# TYPEC0.net
KiCad netlist of a schematic drawn in Altium Designer
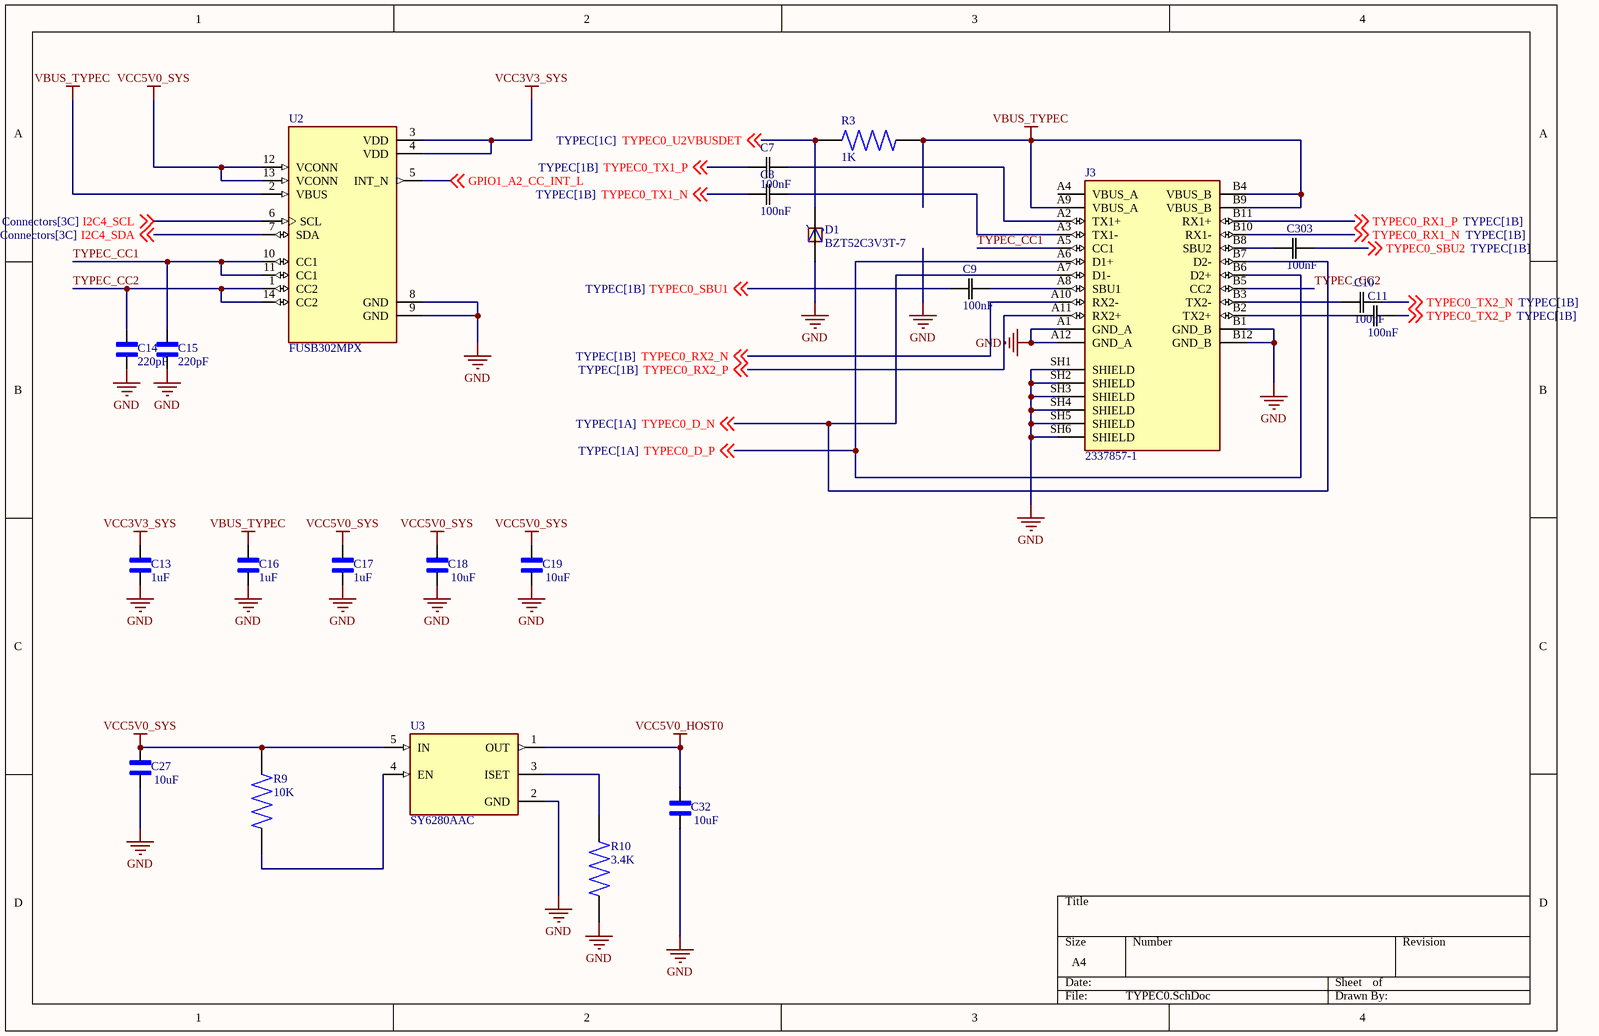
[diagram p0: TYPEC0.SchDoc]

(export (version "E")
  (design (tool "Eeschema 10.0.6"))
  (components
    (comp (ref "C7")
      (value "100nF")
      (footprint "CAP_1005_TDK")
      (description "Description")
      (fields
        (field (name "MANUFACTURER_PART_NUMBER") "C1005X7R1H104M050BB")
        (field (name "COPYRIGHT") "Copyright (C) 2025 Ultra Librarian. All rights reserved.")
      )
      (libsource (lib "C1005X7R1H104M050BB") (part "C1005X7R1H104M050BB"))
    )
    (comp (ref "C8")
      (value "100nF")
      (footprint "CAP_1005_TDK")
      (description "Description")
      (fields
        (field (name "MANUFACTURER_PART_NUMBER") "C1005X7R1H104M050BB")
        (field (name "COPYRIGHT") "Copyright (C) 2025 Ultra Librarian. All rights reserved.")
      )
      (libsource (lib "C1005X7R1H104M050BB") (part "C1005X7R1H104M050BB"))
    )
    (comp (ref "C9")
      (value "100nF")
      (footprint "CAP_1005_TDK")
      (description "Description")
      (fields
        (field (name "MANUFACTURER_PART_NUMBER") "C1005X7R1H104M050BB")
        (field (name "COPYRIGHT") "Copyright (C) 2025 Ultra Librarian. All rights reserved.")
      )
      (libsource (lib "C1005X7R1H104M050BB") (part "C1005X7R1H104M050BB"))
    )
    (comp (ref "C10")
      (value "100nF")
      (footprint "CAP_1005_TDK")
      (description "Description")
      (fields
        (field (name "MANUFACTURER_PART_NUMBER") "C1005X7R1H104M050BB")
        (field (name "COPYRIGHT") "Copyright (C) 2025 Ultra Librarian. All rights reserved.")
      )
      (libsource (lib "C1005X7R1H104M050BB") (part "C1005X7R1H104M050BB"))
    )
    (comp (ref "C11")
      (value "100nF")
      (footprint "CAP_1005_TDK")
      (description "Description")
      (fields
        (field (name "MANUFACTURER_PART_NUMBER") "C1005X7R1H104M050BB")
        (field (name "COPYRIGHT") "Copyright (C) 2025 Ultra Librarian. All rights reserved.")
      )
      (libsource (lib "C1005X7R1H104M050BB") (part "C1005X7R1H104M050BB"))
    )
    (comp (ref "C13")
      (value "1uF")
      (footprint "CAPC1005X56N")
      (description "1 ÂµF Â±10% 10V Ceramic Capacitor X5R 0402 (1005 Metric)")
      (fields (field (name "MF") "AVX") (field (name "MP") "0402ZD105KAT4A"))
      (libsource (lib "0402ZD105KAT4A") (part "0402ZD105KAT4A"))
    )
    (comp (ref "C14")
      (value "220pF")
      (footprint "CAPC1608X90")
      (description "220 pF Â±10% 16V Ceramic Capacitor X7R 0603 (1608 Metric)")
      (fields (field (name "MF") "Yageo") (field (name "MP") "CC0603KRX7R7BB221"))
      (libsource (lib "CC0603KRX7R7BB221") (part "CC0603KRX7R7BB221"))
    )
    (comp (ref "C15")
      (value "220pF")
      (footprint "CAPC1608X90")
      (description "220 pF Â±10% 16V Ceramic Capacitor X7R 0603 (1608 Metric)")
      (fields (field (name "MF") "Yageo") (field (name "MP") "CC0603KRX7R7BB221"))
      (libsource (lib "CC0603KRX7R7BB221") (part "CC0603KRX7R7BB221"))
    )
    (comp (ref "C16")
      (value "1uF")
      (footprint "CAPC1005X56N")
      (description "1 ÂµF Â±10% 10V Ceramic Capacitor X5R 0402 (1005 Metric)")
      (fields (field (name "MF") "AVX") (field (name "MP") "0402ZD105KAT4A"))
      (libsource (lib "0402ZD105KAT4A") (part "0402ZD105KAT4A"))
    )
    (comp (ref "C17")
      (value "1uF")
      (footprint "CAPC1005X56N")
      (description "1 ÂµF Â±10% 10V Ceramic Capacitor X5R 0402 (1005 Metric)")
      (fields (field (name "MF") "AVX") (field (name "MP") "0402ZD105KAT4A"))
      (libsource (lib "0402ZD105KAT4A") (part "0402ZD105KAT4A"))
    )
    (comp (ref "C18")
      (value "10uF")
      (footprint "CAPC1005X70N")
      (description "10 ÂµF Â±20% 6.3V Ceramic Capacitor X5R 0402 (1005 Metric)")
      (fields (field (name "MF") "Samsung") (field (name "MP") "CL05A106MQ5NUNC"))
      (libsource (lib "CL05A106MQ5NUNC") (part "CL05A106MQ5NUNC"))
    )
    (comp (ref "C19")
      (value "10uF")
      (footprint "CAPC1005X70N")
      (description "10 ÂµF Â±20% 6.3V Ceramic Capacitor X5R 0402 (1005 Metric)")
      (fields (field (name "MF") "Samsung") (field (name "MP") "CL05A106MQ5NUNC"))
      (libsource (lib "CL05A106MQ5NUNC") (part "CL05A106MQ5NUNC"))
    )
    (comp (ref "C27")
      (value "10uF")
      (footprint "CAPC1005X70N")
      (description "10 ÂµF Â±20% 6.3V Ceramic Capacitor X5R 0402 (1005 Metric)")
      (fields (field (name "MF") "Samsung") (field (name "MP") "CL05A106MQ5NUNC"))
      (libsource (lib "CL05A106MQ5NUNC") (part "CL05A106MQ5NUNC"))
    )
    (comp (ref "C32")
      (value "10uF")
      (footprint "CAPC1005X70N")
      (description "10 ÂµF Â±20% 6.3V Ceramic Capacitor X5R 0402 (1005 Metric)")
      (fields (field (name "MF") "Samsung") (field (name "MP") "CL05A106MQ5NUNC"))
      (libsource (lib "CL05A106MQ5NUNC") (part "CL05A106MQ5NUNC"))
    )
    (comp (ref "C303")
      (value "100nF")
      (footprint "CAP_1005_TDK")
      (description "Description")
      (fields
        (field (name "MANUFACTURER_PART_NUMBER") "C1005X7R1H104M050BB")
        (field (name "COPYRIGHT") "Copyright (C) 2025 Ultra Librarian. All rights reserved.")
      )
      (libsource (lib "C1005X7R1H104M050BB") (part "C1005X7R1H104M050BB"))
    )
    (comp (ref "D1")
      (value "BZT52C3V3T-7")
      (footprint "SODFL1608X65N")
      (description "3.3V 6% 300mW Zener Diode SOD-523 ¦ Diodes Inc BZT52C3V3T-7")
      (fields (field (name "MF") "Diodes Inc."))
      (libsource (lib "BZT52C3V3T-7") (part "BZT52C3V3T-7"))
    )
    (comp (ref "J3")
      (value "2337857-1")
      (footprint "TE_2337857-1")
      (description "VERTICAL USB TYPE-C REC")
      (fields (field (name "MF") "TE Connectivity"))
      (libsource (lib "2337857-1") (part "2337857-1"))
    )
    (comp (ref "R3")
      (value "1K")
      (footprint "RESC1608X55N")
      (description "1 kOhms Â±1% 0.1W, 1/10W Chip Resistor 0603 (1608 Metric) - Thick Film")
      (fields (field (name "MF") "Vishay") (field (name "MP") "CRCW06031K00FKECC"))
      (libsource (lib "CRCW06031K00FKECC") (part "CRCW06031K00FKECC"))
    )
    (comp (ref "R9")
      (value "10K")
      (footprint "RES_ERA3ARB103V")
      (fields (field (name "MP") "ERA3ARB103V"))
      (libsource (lib "ERA3ARB103V") (part "ERA3ARB103V"))
    )
    (comp (ref "R10")
      (value "3.4K")
      (footprint "RES_ERJPA2F3401X")
      (fields (field (name "MP") "ERJPA2F3401X"))
      (libsource (lib "ERJPA2F3401X") (part "ERJPA2F3401X"))
    )
    (comp (ref "U2")
      (value "FUSB302MPX")
      (footprint "QFN50P250X250X80-15N")
      (description "USB Controller USB 3.1 USB Interface 14-MLP (2.5x2.5)")
      (fields (field (name "MF") "ON Semiconductor"))
      (libsource (lib "FUSB302MPX") (part "FUSB302MPX"))
    )
    (comp (ref "U3")
      (value "SY6280AAC")
      (footprint "SOT95P285X130-5N")
      (description "USB Power Distribution SW Single 5.5V 1A 5-Pin SOT-23")
      (fields (field (name "MF") "Silergy"))
      (libsource (lib "SY6280AAC") (part "SY6280AAC"))
    )
  )
  (nets
    (net (code "1") (name "/TYPEC_CC1") (class "Default")
      (node (ref "C15") (pin "1") (pinfunction "1_1") (pintype "passive"))
      (node (ref "J3") (pin "A5") (pinfunction "CC1_A5") (pintype "bidirectional"))
      (node (ref "U2") (pin "10") (pinfunction "CC1_10") (pintype "bidirectional"))
      (node (ref "U2") (pin "11") (pinfunction "CC1_11") (pintype "bidirectional"))
    )
    (net (code "2") (name "/TYPEC_CC2") (class "Default")
      (node (ref "C14") (pin "1") (pinfunction "1_1") (pintype "passive"))
      (node (ref "J3") (pin "B5") (pinfunction "CC2_B5") (pintype "bidirectional"))
      (node (ref "U2") (pin "1") (pinfunction "CC2_1") (pintype "bidirectional"))
      (node (ref "U2") (pin "14") (pinfunction "CC2_14") (pintype "bidirectional"))
    )
    (net (code "3") (name "GND") (class "Default")
      (node (ref "C13") (pin "1") (pinfunction "1_1") (pintype "passive"))
      (node (ref "C14") (pin "2") (pinfunction "2_2") (pintype "passive"))
      (node (ref "C15") (pin "2") (pinfunction "2_2") (pintype "passive"))
      (node (ref "C16") (pin "1") (pinfunction "1_1") (pintype "passive"))
      (node (ref "C17") (pin "1") (pinfunction "1_1") (pintype "passive"))
      (node (ref "C18") (pin "1") (pinfunction "1_1") (pintype "passive"))
      (node (ref "C19") (pin "1") (pinfunction "1_1") (pintype "passive"))
      (node (ref "C27") (pin "1") (pinfunction "1_1") (pintype "passive"))
      (node (ref "C32") (pin "1") (pinfunction "1_1") (pintype "passive"))
      (node (ref "D1") (pin "A") (pinfunction "A_A") (pintype "passive"))
      (node (ref "J3") (pin "A1") (pinfunction "GND_A_A1") (pintype "power_in"))
      (node (ref "J3") (pin "A12") (pinfunction "GND_A_A12") (pintype "power_in"))
      (node (ref "J3") (pin "B1") (pinfunction "GND_B_B1") (pintype "power_in"))
      (node (ref "J3") (pin "B12") (pinfunction "GND_B_B12") (pintype "power_in"))
      (node (ref "J3") (pin "SH1") (pinfunction "SHIELD_SH1") (pintype "passive"))
      (node (ref "J3") (pin "SH2") (pinfunction "SHIELD_SH2") (pintype "passive"))
      (node (ref "J3") (pin "SH3") (pinfunction "SHIELD_SH3") (pintype "passive"))
      (node (ref "J3") (pin "SH4") (pinfunction "SHIELD_SH4") (pintype "passive"))
      (node (ref "J3") (pin "SH5") (pinfunction "SHIELD_SH5") (pintype "passive"))
      (node (ref "J3") (pin "SH6") (pinfunction "SHIELD_SH6") (pintype "passive"))
      (node (ref "R10") (pin "1") (pinfunction "1_1") (pintype "passive"))
      (node (ref "U2") (pin "8") (pinfunction "GND_8") (pintype "power_in"))
      (node (ref "U2") (pin "9") (pinfunction "GND_9") (pintype "power_in"))
      (node (ref "U3") (pin "2") (pinfunction "GND_2") (pintype "power_in"))
    )
    (net (code "4") (name "GPIO1_A2_CC_INT_L") (class "Default")
      (node (ref "U2") (pin "5") (pinfunction "INT_N_5") (pintype "output"))
    )
    (net (code "5") (name "I2C4_SCL") (class "Default")
      (node (ref "U2") (pin "6") (pinfunction "SCL_6") (pintype "input"))
    )
    (net (code "6") (name "I2C4_SDA") (class "Default")
      (node (ref "U2") (pin "7") (pinfunction "SDA_7") (pintype "bidirectional"))
    )
    (net (code "7") (name "Net-(J3-SBU1)") (class "Default")
      (node (ref "C9") (pin "1") (pinfunction "1_1") (pintype "passive"))
      (node (ref "J3") (pin "A8") (pinfunction "SBU1_A8") (pintype "bidirectional"))
    )
    (net (code "8") (name "Net-(J3-SBU2)") (class "Default")
      (node (ref "C303") (pin "2") (pinfunction "2_2") (pintype "passive"))
      (node (ref "J3") (pin "B8") (pinfunction "SBU2_B8") (pintype "bidirectional"))
    )
    (net (code "9") (name "Net-(J3-TX1+)") (class "Default")
      (node (ref "C7") (pin "1") (pinfunction "1_1") (pintype "passive"))
      (node (ref "J3") (pin "A2") (pinfunction "TX1+_A2") (pintype "bidirectional"))
    )
    (net (code "10") (name "Net-(J3-TX1-)") (class "Default")
      (node (ref "C8") (pin "1") (pinfunction "1_1") (pintype "passive"))
      (node (ref "J3") (pin "A3") (pinfunction "TX1-_A3") (pintype "bidirectional"))
    )
    (net (code "11") (name "Net-(J3-TX2+)") (class "Default")
      (node (ref "C11") (pin "2") (pinfunction "2_2") (pintype "passive"))
      (node (ref "J3") (pin "B2") (pinfunction "TX2+_B2") (pintype "bidirectional"))
    )
    (net (code "12") (name "Net-(J3-TX2-)") (class "Default")
      (node (ref "C10") (pin "2") (pinfunction "2_2") (pintype "passive"))
      (node (ref "J3") (pin "B3") (pinfunction "TX2-_B3") (pintype "bidirectional"))
    )
    (net (code "13") (name "Net-(U3-EN)") (class "Default")
      (node (ref "R9") (pin "1") (pinfunction "1_1") (pintype "passive"))
      (node (ref "U3") (pin "4") (pinfunction "EN_4") (pintype "input"))
    )
    (net (code "14") (name "Net-(U3-ISET)") (class "Default")
      (node (ref "R10") (pin "2") (pinfunction "2_2") (pintype "passive"))
      (node (ref "U3") (pin "3") (pinfunction "ISET_3") (pintype "passive"))
    )
    (net (code "15") (name "TYPEC0_D_N") (class "Default")
      (node (ref "J3") (pin "A7") (pinfunction "D1-_A7") (pintype "bidirectional"))
      (node (ref "J3") (pin "B7") (pinfunction "D2-_B7") (pintype "bidirectional"))
    )
    (net (code "16") (name "TYPEC0_D_P") (class "Default")
      (node (ref "J3") (pin "A6") (pinfunction "D1+_A6") (pintype "bidirectional"))
      (node (ref "J3") (pin "B6") (pinfunction "D2+_B6") (pintype "bidirectional"))
    )
    (net (code "17") (name "TYPEC0_RX1_N") (class "Default")
      (node (ref "J3") (pin "B10") (pinfunction "RX1-_B10") (pintype "bidirectional"))
    )
    (net (code "18") (name "TYPEC0_RX1_P") (class "Default")
      (node (ref "J3") (pin "B11") (pinfunction "RX1+_B11") (pintype "bidirectional"))
    )
    (net (code "19") (name "TYPEC0_RX2_N") (class "Default")
      (node (ref "J3") (pin "A10") (pinfunction "RX2-_A10") (pintype "bidirectional"))
    )
    (net (code "20") (name "TYPEC0_RX2_P") (class "Default")
      (node (ref "J3") (pin "A11") (pinfunction "RX2+_A11") (pintype "bidirectional"))
    )
    (net (code "21") (name "TYPEC0_SBU1") (class "Default")
      (node (ref "C9") (pin "2") (pinfunction "2_2") (pintype "passive"))
    )
    (net (code "22") (name "TYPEC0_SBU2") (class "Default")
      (node (ref "C303") (pin "1") (pinfunction "1_1") (pintype "passive"))
    )
    (net (code "23") (name "TYPEC0_TX1_N") (class "Default")
      (node (ref "C8") (pin "2") (pinfunction "2_2") (pintype "passive"))
    )
    (net (code "24") (name "TYPEC0_TX1_P") (class "Default")
      (node (ref "C7") (pin "2") (pinfunction "2_2") (pintype "passive"))
    )
    (net (code "25") (name "TYPEC0_TX2_N") (class "Default")
      (node (ref "C10") (pin "1") (pinfunction "1_1") (pintype "passive"))
    )
    (net (code "26") (name "TYPEC0_TX2_P") (class "Default")
      (node (ref "C11") (pin "1") (pinfunction "1_1") (pintype "passive"))
    )
    (net (code "27") (name "TYPEC0_U2VBUSDET") (class "Default")
      (node (ref "D1") (pin "C") (pinfunction "C_C") (pintype "passive"))
      (node (ref "R3") (pin "1") (pinfunction "1_1") (pintype "passive"))
    )
    (net (code "28") (name "VBUS_TYPEC") (class "Default")
      (node (ref "C16") (pin "2") (pinfunction "2_2") (pintype "passive"))
      (node (ref "J3") (pin "A9") (pinfunction "VBUS_A_A9") (pintype "power_in"))
      (node (ref "J3") (pin "B4") (pinfunction "VBUS_B_B4") (pintype "power_in"))
      (node (ref "J3") (pin "B9") (pinfunction "VBUS_B_B9") (pintype "power_in"))
      (node (ref "R3") (pin "2") (pinfunction "2_2") (pintype "passive"))
      (node (ref "U2") (pin "2") (pinfunction "VBUS_2") (pintype "input"))
    )
    (net (code "29") (name "VCC3V3_SYS") (class "Default")
      (node (ref "C13") (pin "2") (pinfunction "2_2") (pintype "passive"))
      (node (ref "U2") (pin "3") (pinfunction "VDD_3") (pintype "power_in"))
      (node (ref "U2") (pin "4") (pinfunction "VDD_4") (pintype "power_in"))
    )
    (net (code "30") (name "VCC5V0_HOST0") (class "Default")
      (node (ref "C32") (pin "2") (pinfunction "2_2") (pintype "passive"))
      (node (ref "U3") (pin "1") (pinfunction "OUT_1") (pintype "output"))
    )
    (net (code "31") (name "VCC5V0_SYS") (class "Default")
      (node (ref "C17") (pin "2") (pinfunction "2_2") (pintype "passive"))
      (node (ref "C18") (pin "2") (pinfunction "2_2") (pintype "passive"))
      (node (ref "C19") (pin "2") (pinfunction "2_2") (pintype "passive"))
      (node (ref "C27") (pin "2") (pinfunction "2_2") (pintype "passive"))
      (node (ref "R9") (pin "2") (pinfunction "2_2") (pintype "passive"))
      (node (ref "U2") (pin "12") (pinfunction "VCONN_12") (pintype "input"))
      (node (ref "U2") (pin "13") (pinfunction "VCONN_13") (pintype "input"))
      (node (ref "U3") (pin "5") (pinfunction "IN_5") (pintype "input"))
    )
    (net (code "32") (name "unconnected-(J3-VBUS_A-PadA4)") (class "Default")
      (node (ref "J3") (pin "A4") (pinfunction "VBUS_A_A4") (pintype "power_in"))
    )
  )
)
